# XC7A35TFTG256_power.net
KiCad netlist of a schematic drawn in Altium Designer
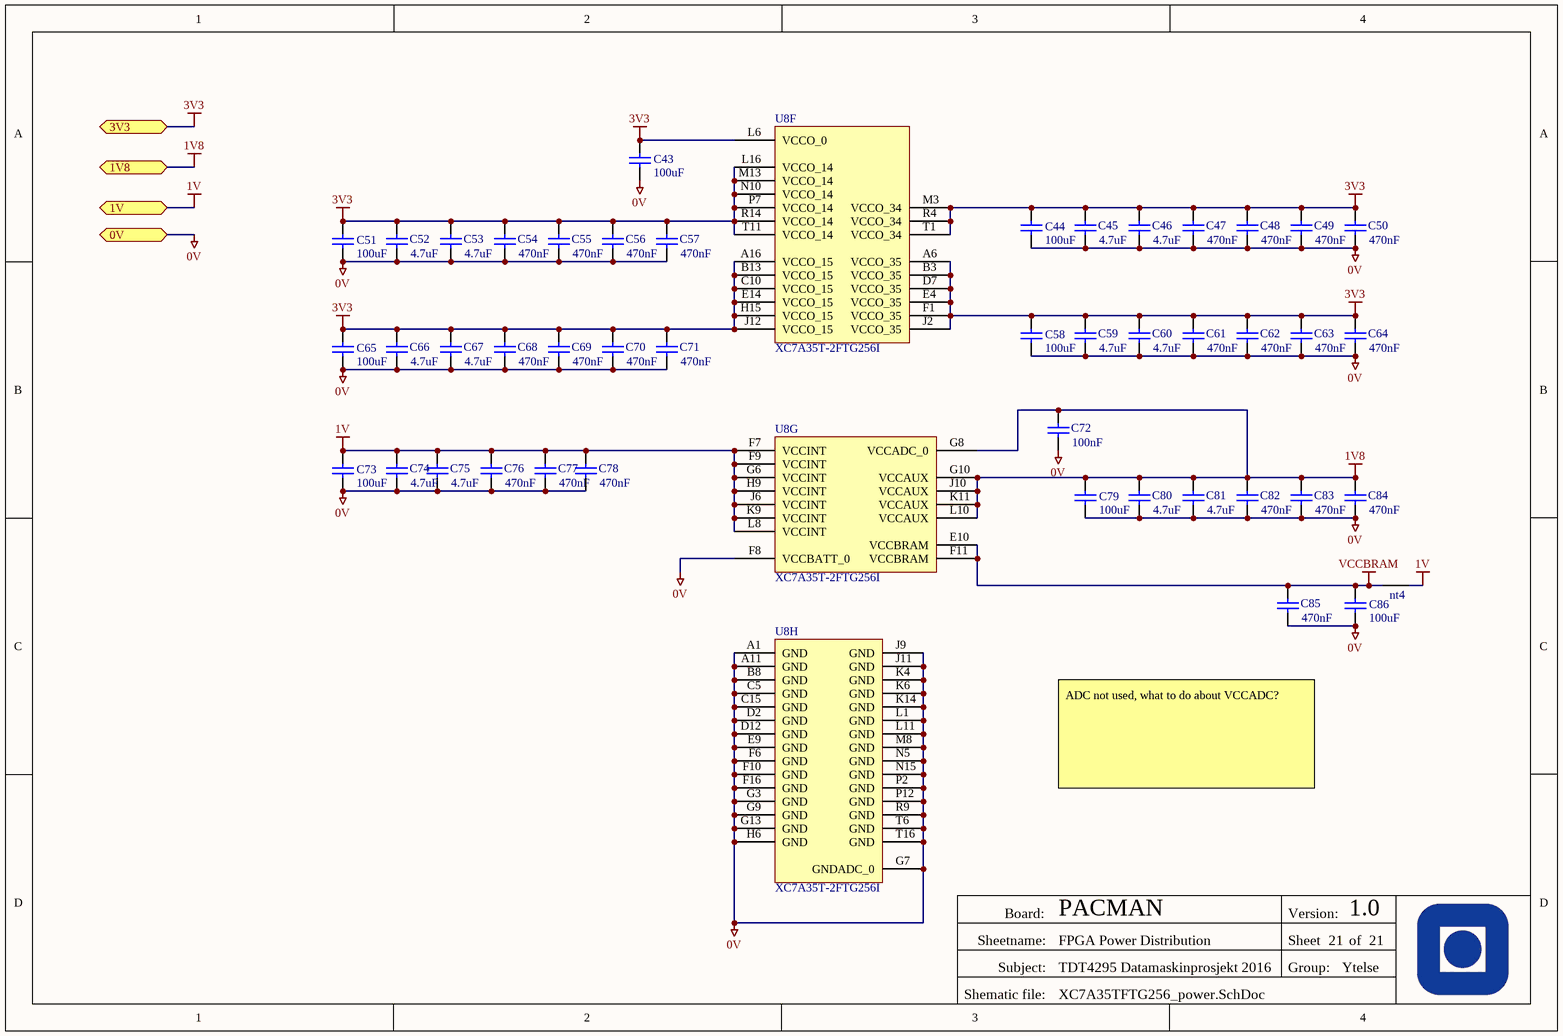
[diagram p0: XC7A35TFTG256_power.SchDoc]

(export (version "E")
  (design (tool "Eeschema 10.0.6"))
  (components
    (comp (ref "C43")
      (value "100uF")
      (footprint "CAPC1210(3225)250_N")
      (description "1210 100uF capacitor for artix-7 power decoupling")
      (fields (field (name "Comment") "GRM32ER60J107ME20L"))
      (libsource (lib "dmpro16lib") (part "GRM32ER60J107ME20L"))
    )
    (comp (ref "C44")
      (value "100uF")
      (footprint "CAPC1210(3225)250_N")
      (description "1210 100uF capacitor for artix-7 power decoupling")
      (fields (field (name "Comment") "GRM32ER60J107ME20L"))
      (libsource (lib "dmpro16lib") (part "GRM32ER60J107ME20L"))
    )
    (comp (ref "C45")
      (value "4.7uF")
      (footprint "CAPC0603(1608)100_M")
      (description "CAP 4.7uF 10V ±10% 0603 (1608 Metric) Thickness 1mm SMD")
      (fields (field (name "TOLERANCE") "Â±10%") (field (name "Comment") "CAP 4.7uF 10V 0603(1608)"))
      (libsource (lib "Altium Content Vault") (part "CMP-1035-02785-1"))
    )
    (comp (ref "C46")
      (value "4.7uF")
      (footprint "CAPC0603(1608)100_M")
      (description "CAP 4.7uF 10V ±10% 0603 (1608 Metric) Thickness 1mm SMD")
      (fields (field (name "TOLERANCE") "Â±10%") (field (name "Comment") "CAP 4.7uF 10V 0603(1608)"))
      (libsource (lib "Altium Content Vault") (part "CMP-1035-02785-1"))
    )
    (comp (ref "C47")
      (value "470nF")
      (footprint "CAPC0603(1608)100_L")
      (description "CAP 470nF 10V ±5% 0603 (1608 Metric) Thickness 1mm SMD")
      (fields (field (name "TOLERANCE") "Â±5%") (field (name "Comment") "CAP 470nF 10V 0603(1608)"))
      (libsource (lib "Altium Content Vault") (part "CMP-1035-02695-1"))
    )
    (comp (ref "C48")
      (value "470nF")
      (footprint "CAPC0603(1608)100_L")
      (description "CAP 470nF 10V ±5% 0603 (1608 Metric) Thickness 1mm SMD")
      (fields (field (name "TOLERANCE") "Â±5%") (field (name "Comment") "CAP 470nF 10V 0603(1608)"))
      (libsource (lib "Altium Content Vault") (part "CMP-1035-02695-1"))
    )
    (comp (ref "C49")
      (value "470nF")
      (footprint "CAPC0603(1608)100_L")
      (description "CAP 470nF 10V ±5% 0603 (1608 Metric) Thickness 1mm SMD")
      (fields (field (name "TOLERANCE") "Â±5%") (field (name "Comment") "CAP 470nF 10V 0603(1608)"))
      (libsource (lib "Altium Content Vault") (part "CMP-1035-02695-1"))
    )
    (comp (ref "C50")
      (value "470nF")
      (footprint "CAPC0603(1608)100_L")
      (description "CAP 470nF 10V ±5% 0603 (1608 Metric) Thickness 1mm SMD")
      (fields (field (name "TOLERANCE") "Â±5%") (field (name "Comment") "CAP 470nF 10V 0603(1608)"))
      (libsource (lib "Altium Content Vault") (part "CMP-1035-02695-1"))
    )
    (comp (ref "C51")
      (value "100uF")
      (footprint "CAPC1210(3225)250_N")
      (description "1210 100uF capacitor for artix-7 power decoupling")
      (fields (field (name "Comment") "GRM32ER60J107ME20L"))
      (libsource (lib "dmpro16lib") (part "GRM32ER60J107ME20L"))
    )
    (comp (ref "C52")
      (value "4.7uF")
      (footprint "CAPC0603(1608)100_M")
      (description "CAP 4.7uF 10V ±10% 0603 (1608 Metric) Thickness 1mm SMD")
      (fields (field (name "TOLERANCE") "Â±10%") (field (name "Comment") "CAP 4.7uF 10V 0603(1608)"))
      (libsource (lib "Altium Content Vault") (part "CMP-1035-02785-1"))
    )
    (comp (ref "C53")
      (value "4.7uF")
      (footprint "CAPC0603(1608)100_M")
      (description "CAP 4.7uF 10V ±10% 0603 (1608 Metric) Thickness 1mm SMD")
      (fields (field (name "TOLERANCE") "Â±10%") (field (name "Comment") "CAP 4.7uF 10V 0603(1608)"))
      (libsource (lib "Altium Content Vault") (part "CMP-1035-02785-1"))
    )
    (comp (ref "C54")
      (value "470nF")
      (footprint "CAPC0603(1608)100_L")
      (description "CAP 470nF 10V ±5% 0603 (1608 Metric) Thickness 1mm SMD")
      (fields (field (name "TOLERANCE") "Â±5%") (field (name "Comment") "CAP 470nF 10V 0603(1608)"))
      (libsource (lib "Altium Content Vault") (part "CMP-1035-02695-1"))
    )
    (comp (ref "C55")
      (value "470nF")
      (footprint "CAPC0603(1608)100_L")
      (description "CAP 470nF 10V ±5% 0603 (1608 Metric) Thickness 1mm SMD")
      (fields (field (name "TOLERANCE") "Â±5%") (field (name "Comment") "CAP 470nF 10V 0603(1608)"))
      (libsource (lib "Altium Content Vault") (part "CMP-1035-02695-1"))
    )
    (comp (ref "C56")
      (value "470nF")
      (footprint "CAPC0603(1608)100_L")
      (description "CAP 470nF 10V ±5% 0603 (1608 Metric) Thickness 1mm SMD")
      (fields (field (name "TOLERANCE") "Â±5%") (field (name "Comment") "CAP 470nF 10V 0603(1608)"))
      (libsource (lib "Altium Content Vault") (part "CMP-1035-02695-1"))
    )
    (comp (ref "C57")
      (value "470nF")
      (footprint "CAPC0603(1608)100_L")
      (description "CAP 470nF 10V ±5% 0603 (1608 Metric) Thickness 1mm SMD")
      (fields (field (name "TOLERANCE") "Â±5%") (field (name "Comment") "CAP 470nF 10V 0603(1608)"))
      (libsource (lib "Altium Content Vault") (part "CMP-1035-02695-1"))
    )
    (comp (ref "C58")
      (value "100uF")
      (footprint "CAPC1210(3225)250_N")
      (description "1210 100uF capacitor for artix-7 power decoupling")
      (fields (field (name "Comment") "GRM32ER60J107ME20L"))
      (libsource (lib "dmpro16lib") (part "GRM32ER60J107ME20L"))
    )
    (comp (ref "C59")
      (value "4.7uF")
      (footprint "CAPC0603(1608)100_M")
      (description "CAP 4.7uF 10V ±10% 0603 (1608 Metric) Thickness 1mm SMD")
      (fields (field (name "TOLERANCE") "Â±10%") (field (name "Comment") "CAP 4.7uF 10V 0603(1608)"))
      (libsource (lib "Altium Content Vault") (part "CMP-1035-02785-1"))
    )
    (comp (ref "C60")
      (value "4.7uF")
      (footprint "CAPC0603(1608)100_M")
      (description "CAP 4.7uF 10V ±10% 0603 (1608 Metric) Thickness 1mm SMD")
      (fields (field (name "TOLERANCE") "Â±10%") (field (name "Comment") "CAP 4.7uF 10V 0603(1608)"))
      (libsource (lib "Altium Content Vault") (part "CMP-1035-02785-1"))
    )
    (comp (ref "C61")
      (value "470nF")
      (footprint "CAPC0603(1608)100_L")
      (description "CAP 470nF 10V ±5% 0603 (1608 Metric) Thickness 1mm SMD")
      (fields (field (name "TOLERANCE") "Â±5%") (field (name "Comment") "CAP 470nF 10V 0603(1608)"))
      (libsource (lib "Altium Content Vault") (part "CMP-1035-02695-1"))
    )
    (comp (ref "C62")
      (value "470nF")
      (footprint "CAPC0603(1608)100_L")
      (description "CAP 470nF 10V ±5% 0603 (1608 Metric) Thickness 1mm SMD")
      (fields (field (name "TOLERANCE") "Â±5%") (field (name "Comment") "CAP 470nF 10V 0603(1608)"))
      (libsource (lib "Altium Content Vault") (part "CMP-1035-02695-1"))
    )
    (comp (ref "C63")
      (value "470nF")
      (footprint "CAPC0603(1608)100_L")
      (description "CAP 470nF 10V ±5% 0603 (1608 Metric) Thickness 1mm SMD")
      (fields (field (name "TOLERANCE") "Â±5%") (field (name "Comment") "CAP 470nF 10V 0603(1608)"))
      (libsource (lib "Altium Content Vault") (part "CMP-1035-02695-1"))
    )
    (comp (ref "C64")
      (value "470nF")
      (footprint "CAPC0603(1608)100_L")
      (description "CAP 470nF 10V ±5% 0603 (1608 Metric) Thickness 1mm SMD")
      (fields (field (name "TOLERANCE") "Â±5%") (field (name "Comment") "CAP 470nF 10V 0603(1608)"))
      (libsource (lib "Altium Content Vault") (part "CMP-1035-02695-1"))
    )
    (comp (ref "C65")
      (value "100uF")
      (footprint "CAPC1210(3225)250_N")
      (description "1210 100uF capacitor for artix-7 power decoupling")
      (fields (field (name "Comment") "GRM32ER60J107ME20L"))
      (libsource (lib "dmpro16lib") (part "GRM32ER60J107ME20L"))
    )
    (comp (ref "C66")
      (value "4.7uF")
      (footprint "CAPC0603(1608)100_M")
      (description "CAP 4.7uF 10V ±10% 0603 (1608 Metric) Thickness 1mm SMD")
      (fields (field (name "TOLERANCE") "Â±10%") (field (name "Comment") "CAP 4.7uF 10V 0603(1608)"))
      (libsource (lib "Altium Content Vault") (part "CMP-1035-02785-1"))
    )
    (comp (ref "C67")
      (value "4.7uF")
      (footprint "CAPC0603(1608)100_M")
      (description "CAP 4.7uF 10V ±10% 0603 (1608 Metric) Thickness 1mm SMD")
      (fields (field (name "TOLERANCE") "Â±10%") (field (name "Comment") "CAP 4.7uF 10V 0603(1608)"))
      (libsource (lib "Altium Content Vault") (part "CMP-1035-02785-1"))
    )
    (comp (ref "C68")
      (value "470nF")
      (footprint "CAPC0603(1608)100_L")
      (description "CAP 470nF 10V ±5% 0603 (1608 Metric) Thickness 1mm SMD")
      (fields (field (name "TOLERANCE") "Â±5%") (field (name "Comment") "CAP 470nF 10V 0603(1608)"))
      (libsource (lib "Altium Content Vault") (part "CMP-1035-02695-1"))
    )
    (comp (ref "C69")
      (value "470nF")
      (footprint "CAPC0603(1608)100_L")
      (description "CAP 470nF 10V ±5% 0603 (1608 Metric) Thickness 1mm SMD")
      (fields (field (name "TOLERANCE") "Â±5%") (field (name "Comment") "CAP 470nF 10V 0603(1608)"))
      (libsource (lib "Altium Content Vault") (part "CMP-1035-02695-1"))
    )
    (comp (ref "C70")
      (value "470nF")
      (footprint "CAPC0603(1608)100_L")
      (description "CAP 470nF 10V ±5% 0603 (1608 Metric) Thickness 1mm SMD")
      (fields (field (name "TOLERANCE") "Â±5%") (field (name "Comment") "CAP 470nF 10V 0603(1608)"))
      (libsource (lib "Altium Content Vault") (part "CMP-1035-02695-1"))
    )
    (comp (ref "C71")
      (value "470nF")
      (footprint "CAPC0603(1608)100_L")
      (description "CAP 470nF 10V ±5% 0603 (1608 Metric) Thickness 1mm SMD")
      (fields (field (name "TOLERANCE") "Â±5%") (field (name "Comment") "CAP 470nF 10V 0603(1608)"))
      (libsource (lib "Altium Content Vault") (part "CMP-1035-02695-1"))
    )
    (comp (ref "C72")
      (value "100nF")
      (footprint "CAPC0603(1608)100_M")
      (description "CAP 100nF 16V ±5% 0603 (1608 Metric) Thickness 1mm SMD")
      (fields (field (name "TOLERANCE") "Â±5%") (field (name "Comment") "CAP 100nF 16V 0603(1608)"))
      (libsource (lib "Altium Content Vault") (part "CMP-1035-02583-1"))
    )
    (comp (ref "C73")
      (value "100uF")
      (footprint "CAPC1210(3225)250_N")
      (description "1210 100uF capacitor for artix-7 power decoupling")
      (fields (field (name "Comment") "GRM32ER60J107ME20L"))
      (libsource (lib "dmpro16lib") (part "GRM32ER60J107ME20L"))
    )
    (comp (ref "C74")
      (value "4.7uF")
      (footprint "CAPC0603(1608)100_M")
      (description "CAP 4.7uF 10V ±10% 0603 (1608 Metric) Thickness 1mm SMD")
      (fields (field (name "TOLERANCE") "Â±10%") (field (name "Comment") "CAP 4.7uF 10V 0603(1608)"))
      (libsource (lib "Altium Content Vault") (part "CMP-1035-02785-1"))
    )
    (comp (ref "C75")
      (value "4.7uF")
      (footprint "CAPC0603(1608)100_M")
      (description "CAP 4.7uF 10V ±10% 0603 (1608 Metric) Thickness 1mm SMD")
      (fields (field (name "TOLERANCE") "Â±10%") (field (name "Comment") "CAP 4.7uF 10V 0603(1608)"))
      (libsource (lib "Altium Content Vault") (part "CMP-1035-02785-1"))
    )
    (comp (ref "C76")
      (value "470nF")
      (footprint "CAPC0603(1608)100_L")
      (description "CAP 470nF 10V ±5% 0603 (1608 Metric) Thickness 1mm SMD")
      (fields (field (name "TOLERANCE") "Â±5%") (field (name "Comment") "CAP 470nF 10V 0603(1608)"))
      (libsource (lib "Altium Content Vault") (part "CMP-1035-02695-1"))
    )
    (comp (ref "C77")
      (value "470nF")
      (footprint "CAPC0603(1608)100_L")
      (description "CAP 470nF 10V ±5% 0603 (1608 Metric) Thickness 1mm SMD")
      (fields (field (name "TOLERANCE") "Â±5%") (field (name "Comment") "CAP 470nF 10V 0603(1608)"))
      (libsource (lib "Altium Content Vault") (part "CMP-1035-02695-1"))
    )
    (comp (ref "C78")
      (value "470nF")
      (footprint "CAPC0603(1608)100_L")
      (description "CAP 470nF 10V ±5% 0603 (1608 Metric) Thickness 1mm SMD")
      (fields (field (name "TOLERANCE") "Â±5%") (field (name "Comment") "CAP 470nF 10V 0603(1608)"))
      (libsource (lib "Altium Content Vault") (part "CMP-1035-02695-1"))
    )
    (comp (ref "C79")
      (value "100uF")
      (footprint "CAPC1210(3225)250_N")
      (description "1210 100uF capacitor for artix-7 power decoupling")
      (fields (field (name "Comment") "GRM32ER60J107ME20L"))
      (libsource (lib "dmpro16lib") (part "GRM32ER60J107ME20L"))
    )
    (comp (ref "C80")
      (value "4.7uF")
      (footprint "CAPC0603(1608)100_M")
      (description "CAP 4.7uF 10V ±10% 0603 (1608 Metric) Thickness 1mm SMD")
      (fields (field (name "TOLERANCE") "Â±10%") (field (name "Comment") "CAP 4.7uF 10V 0603(1608)"))
      (libsource (lib "Altium Content Vault") (part "CMP-1035-02785-1"))
    )
    (comp (ref "C81")
      (value "4.7uF")
      (footprint "CAPC0603(1608)100_M")
      (description "CAP 4.7uF 10V ±10% 0603 (1608 Metric) Thickness 1mm SMD")
      (fields (field (name "TOLERANCE") "Â±10%") (field (name "Comment") "CAP 4.7uF 10V 0603(1608)"))
      (libsource (lib "Altium Content Vault") (part "CMP-1035-02785-1"))
    )
    (comp (ref "C82")
      (value "470nF")
      (footprint "CAPC0603(1608)100_L")
      (description "CAP 470nF 10V ±5% 0603 (1608 Metric) Thickness 1mm SMD")
      (fields (field (name "TOLERANCE") "Â±5%") (field (name "Comment") "CAP 470nF 10V 0603(1608)"))
      (libsource (lib "Altium Content Vault") (part "CMP-1035-02695-1"))
    )
    (comp (ref "C83")
      (value "470nF")
      (footprint "CAPC0603(1608)100_L")
      (description "CAP 470nF 10V ±5% 0603 (1608 Metric) Thickness 1mm SMD")
      (fields (field (name "TOLERANCE") "Â±5%") (field (name "Comment") "CAP 470nF 10V 0603(1608)"))
      (libsource (lib "Altium Content Vault") (part "CMP-1035-02695-1"))
    )
    (comp (ref "C84")
      (value "470nF")
      (footprint "CAPC0603(1608)100_L")
      (description "CAP 470nF 10V ±5% 0603 (1608 Metric) Thickness 1mm SMD")
      (fields (field (name "TOLERANCE") "Â±5%") (field (name "Comment") "CAP 470nF 10V 0603(1608)"))
      (libsource (lib "Altium Content Vault") (part "CMP-1035-02695-1"))
    )
    (comp (ref "C85")
      (value "470nF")
      (footprint "CAPC0603(1608)100_L")
      (description "CAP 470nF 10V ±5% 0603 (1608 Metric) Thickness 1mm SMD")
      (fields (field (name "TOLERANCE") "Â±5%") (field (name "Comment") "CAP 470nF 10V 0603(1608)"))
      (libsource (lib "Altium Content Vault") (part "CMP-1035-02695-1"))
    )
    (comp (ref "C86")
      (value "100uF")
      (footprint "CAPC1210(3225)250_N")
      (description "1210 100uF capacitor for artix-7 power decoupling")
      (fields (field (name "Comment") "GRM32ER60J107ME20L"))
      (libsource (lib "dmpro16lib") (part "GRM32ER60J107ME20L"))
    )
    (comp (ref "nt4")
      (value "net tie")
      (footprint "net tie")
      (description "used to connect nets without transferring net name")
      (libsource (lib "dmpro16lib") (part "net tie"))
    )
    (comp (ref "U8")
      (value "XC7A35T-2FTG256I")
      (footprint "FTG256")
      (description "Artix-7 FPGA, 170 User I/Os, 0 GTP, 256-Ball BGA, Speed Grade 2, Industrial Grade, Pb-Free")
      (fields (field (name "MANUFACTURER") "Xilinx"))
      (libsource (lib "Altium Content Vault") (part "XLNX-XC7A35T-FTG256"))
    )
  )
  (nets
    (net (code "1") (name "0V") (class "Default")
      (node (ref "C43") (pin "1") (pinfunction "1_1") (pintype "passive"))
      (node (ref "C44") (pin "1") (pinfunction "1_1") (pintype "passive"))
      (node (ref "C45") (pin "1") (pinfunction "1_1") (pintype "passive"))
      (node (ref "C46") (pin "1") (pinfunction "1_1") (pintype "passive"))
      (node (ref "C47") (pin "1") (pinfunction "1_1") (pintype "passive"))
      (node (ref "C48") (pin "1") (pinfunction "1_1") (pintype "passive"))
      (node (ref "C49") (pin "1") (pinfunction "1_1") (pintype "passive"))
      (node (ref "C50") (pin "1") (pinfunction "1_1") (pintype "passive"))
      (node (ref "C51") (pin "1") (pinfunction "1_1") (pintype "passive"))
      (node (ref "C52") (pin "1") (pinfunction "1_1") (pintype "passive"))
      (node (ref "C53") (pin "1") (pinfunction "1_1") (pintype "passive"))
      (node (ref "C54") (pin "1") (pinfunction "1_1") (pintype "passive"))
      (node (ref "C55") (pin "1") (pinfunction "1_1") (pintype "passive"))
      (node (ref "C56") (pin "1") (pinfunction "1_1") (pintype "passive"))
      (node (ref "C57") (pin "1") (pinfunction "1_1") (pintype "passive"))
      (node (ref "C58") (pin "1") (pinfunction "1_1") (pintype "passive"))
      (node (ref "C59") (pin "1") (pinfunction "1_1") (pintype "passive"))
      (node (ref "C60") (pin "1") (pinfunction "1_1") (pintype "passive"))
      (node (ref "C61") (pin "1") (pinfunction "1_1") (pintype "passive"))
      (node (ref "C62") (pin "1") (pinfunction "1_1") (pintype "passive"))
      (node (ref "C63") (pin "1") (pinfunction "1_1") (pintype "passive"))
      (node (ref "C64") (pin "1") (pinfunction "1_1") (pintype "passive"))
      (node (ref "C65") (pin "1") (pinfunction "1_1") (pintype "passive"))
      (node (ref "C66") (pin "1") (pinfunction "1_1") (pintype "passive"))
      (node (ref "C67") (pin "1") (pinfunction "1_1") (pintype "passive"))
      (node (ref "C68") (pin "1") (pinfunction "1_1") (pintype "passive"))
      (node (ref "C69") (pin "1") (pinfunction "1_1") (pintype "passive"))
      (node (ref "C70") (pin "1") (pinfunction "1_1") (pintype "passive"))
      (node (ref "C71") (pin "1") (pinfunction "1_1") (pintype "passive"))
      (node (ref "C72") (pin "1") (pinfunction "1_1") (pintype "passive"))
      (node (ref "C73") (pin "1") (pinfunction "1_1") (pintype "passive"))
      (node (ref "C74") (pin "1") (pinfunction "1_1") (pintype "passive"))
      (node (ref "C75") (pin "1") (pinfunction "1_1") (pintype "passive"))
      (node (ref "C76") (pin "1") (pinfunction "1_1") (pintype "passive"))
      (node (ref "C77") (pin "1") (pinfunction "1_1") (pintype "passive"))
      (node (ref "C78") (pin "1") (pinfunction "1_1") (pintype "passive"))
      (node (ref "C79") (pin "1") (pinfunction "1_1") (pintype "passive"))
      (node (ref "C80") (pin "1") (pinfunction "1_1") (pintype "passive"))
      (node (ref "C81") (pin "1") (pinfunction "1_1") (pintype "passive"))
      (node (ref "C82") (pin "1") (pinfunction "1_1") (pintype "passive"))
      (node (ref "C83") (pin "1") (pinfunction "1_1") (pintype "passive"))
      (node (ref "C84") (pin "1") (pinfunction "1_1") (pintype "passive"))
      (node (ref "C85") (pin "1") (pinfunction "1_1") (pintype "passive"))
      (node (ref "C86") (pin "1") (pinfunction "1_1") (pintype "passive"))
      (node (ref "U8") (pin "A1") (pinfunction "GND_A1") (pintype "power_in"))
      (node (ref "U8") (pin "A11") (pinfunction "GND_A11") (pintype "power_in"))
      (node (ref "U8") (pin "B8") (pinfunction "GND_B8") (pintype "power_in"))
      (node (ref "U8") (pin "C15") (pinfunction "GND_C15") (pintype "power_in"))
      (node (ref "U8") (pin "C5") (pinfunction "GND_C5") (pintype "power_in"))
      (node (ref "U8") (pin "D12") (pinfunction "GND_D12") (pintype "power_in"))
      (node (ref "U8") (pin "D2") (pinfunction "GND_D2") (pintype "power_in"))
      (node (ref "U8") (pin "E9") (pinfunction "GND_E9") (pintype "power_in"))
      (node (ref "U8") (pin "F10") (pinfunction "GND_F10") (pintype "power_in"))
      (node (ref "U8") (pin "F16") (pinfunction "GND_F16") (pintype "power_in"))
      (node (ref "U8") (pin "F6") (pinfunction "GND_F6") (pintype "power_in"))
      (node (ref "U8") (pin "F8") (pinfunction "VCCBATT_0_F8") (pintype "power_in"))
      (node (ref "U8") (pin "G13") (pinfunction "GND_G13") (pintype "power_in"))
      (node (ref "U8") (pin "G3") (pinfunction "GND_G3") (pintype "power_in"))
      (node (ref "U8") (pin "G7") (pinfunction "GNDADC_0_G7") (pintype "power_in"))
      (node (ref "U8") (pin "G9") (pinfunction "GND_G9") (pintype "power_in"))
      (node (ref "U8") (pin "H6") (pinfunction "GND_H6") (pintype "power_in"))
      (node (ref "U8") (pin "J11") (pinfunction "GND_J11") (pintype "power_in"))
      (node (ref "U8") (pin "J9") (pinfunction "GND_J9") (pintype "power_in"))
      (node (ref "U8") (pin "K14") (pinfunction "GND_K14") (pintype "power_in"))
      (node (ref "U8") (pin "K4") (pinfunction "GND_K4") (pintype "power_in"))
      (node (ref "U8") (pin "K6") (pinfunction "GND_K6") (pintype "power_in"))
      (node (ref "U8") (pin "L1") (pinfunction "GND_L1") (pintype "power_in"))
      (node (ref "U8") (pin "L11") (pinfunction "GND_L11") (pintype "power_in"))
      (node (ref "U8") (pin "M8") (pinfunction "GND_M8") (pintype "power_in"))
      (node (ref "U8") (pin "N15") (pinfunction "GND_N15") (pintype "power_in"))
      (node (ref "U8") (pin "N5") (pinfunction "GND_N5") (pintype "power_in"))
      (node (ref "U8") (pin "P12") (pinfunction "GND_P12") (pintype "power_in"))
      (node (ref "U8") (pin "P2") (pinfunction "GND_P2") (pintype "power_in"))
      (node (ref "U8") (pin "R9") (pinfunction "GND_R9") (pintype "power_in"))
      (node (ref "U8") (pin "T16") (pinfunction "GND_T16") (pintype "power_in"))
      (node (ref "U8") (pin "T6") (pinfunction "GND_T6") (pintype "power_in"))
    )
    (net (code "2") (name "1V") (class "Default")
      (node (ref "C73") (pin "2") (pinfunction "2_2") (pintype "passive"))
      (node (ref "C74") (pin "2") (pinfunction "2_2") (pintype "passive"))
      (node (ref "C75") (pin "2") (pinfunction "2_2") (pintype "passive"))
      (node (ref "C76") (pin "2") (pinfunction "2_2") (pintype "passive"))
      (node (ref "C77") (pin "2") (pinfunction "2_2") (pintype "passive"))
      (node (ref "C78") (pin "2") (pinfunction "2_2") (pintype "passive"))
      (node (ref "U8") (pin "F7") (pinfunction "VCCINT_F7") (pintype "power_in"))
      (node (ref "U8") (pin "F9") (pinfunction "VCCINT_F9") (pintype "power_in"))
      (node (ref "U8") (pin "G6") (pinfunction "VCCINT_G6") (pintype "power_in"))
      (node (ref "U8") (pin "H9") (pinfunction "VCCINT_H9") (pintype "power_in"))
      (node (ref "U8") (pin "J6") (pinfunction "VCCINT_J6") (pintype "power_in"))
      (node (ref "U8") (pin "K9") (pinfunction "VCCINT_K9") (pintype "power_in"))
      (node (ref "U8") (pin "L8") (pinfunction "VCCINT_L8") (pintype "power_in"))
      (node (ref "nt4") (pin "1") (pinfunction "1_1") (pintype "passive"))
    )
    (net (code "3") (name "1V8") (class "Default")
      (node (ref "C72") (pin "2") (pinfunction "2_2") (pintype "passive"))
      (node (ref "C79") (pin "2") (pinfunction "2_2") (pintype "passive"))
      (node (ref "C80") (pin "2") (pinfunction "2_2") (pintype "passive"))
      (node (ref "C81") (pin "2") (pinfunction "2_2") (pintype "passive"))
      (node (ref "C82") (pin "2") (pinfunction "2_2") (pintype "passive"))
      (node (ref "C83") (pin "2") (pinfunction "2_2") (pintype "passive"))
      (node (ref "C84") (pin "2") (pinfunction "2_2") (pintype "passive"))
      (node (ref "U8") (pin "G10") (pinfunction "VCCAUX_G10") (pintype "power_in"))
      (node (ref "U8") (pin "G8") (pinfunction "VCCADC_0_G8") (pintype "power_in"))
      (node (ref "U8") (pin "J10") (pinfunction "VCCAUX_J10") (pintype "power_in"))
      (node (ref "U8") (pin "K11") (pinfunction "VCCAUX_K11") (pintype "power_in"))
      (node (ref "U8") (pin "L10") (pinfunction "VCCAUX_L10") (pintype "power_in"))
    )
    (net (code "4") (name "3V3") (class "Default")
      (node (ref "C43") (pin "2") (pinfunction "2_2") (pintype "passive"))
      (node (ref "C44") (pin "2") (pinfunction "2_2") (pintype "passive"))
      (node (ref "C45") (pin "2") (pinfunction "2_2") (pintype "passive"))
      (node (ref "C46") (pin "2") (pinfunction "2_2") (pintype "passive"))
      (node (ref "C47") (pin "2") (pinfunction "2_2") (pintype "passive"))
      (node (ref "C48") (pin "2") (pinfunction "2_2") (pintype "passive"))
      (node (ref "C49") (pin "2") (pinfunction "2_2") (pintype "passive"))
      (node (ref "C50") (pin "2") (pinfunction "2_2") (pintype "passive"))
      (node (ref "C51") (pin "2") (pinfunction "2_2") (pintype "passive"))
      (node (ref "C52") (pin "2") (pinfunction "2_2") (pintype "passive"))
      (node (ref "C53") (pin "2") (pinfunction "2_2") (pintype "passive"))
      (node (ref "C54") (pin "2") (pinfunction "2_2") (pintype "passive"))
      (node (ref "C55") (pin "2") (pinfunction "2_2") (pintype "passive"))
      (node (ref "C56") (pin "2") (pinfunction "2_2") (pintype "passive"))
      (node (ref "C57") (pin "2") (pinfunction "2_2") (pintype "passive"))
      (node (ref "C58") (pin "2") (pinfunction "2_2") (pintype "passive"))
      (node (ref "C59") (pin "2") (pinfunction "2_2") (pintype "passive"))
      (node (ref "C60") (pin "2") (pinfunction "2_2") (pintype "passive"))
      (node (ref "C61") (pin "2") (pinfunction "2_2") (pintype "passive"))
      (node (ref "C62") (pin "2") (pinfunction "2_2") (pintype "passive"))
      (node (ref "C63") (pin "2") (pinfunction "2_2") (pintype "passive"))
      (node (ref "C64") (pin "2") (pinfunction "2_2") (pintype "passive"))
      (node (ref "C65") (pin "2") (pinfunction "2_2") (pintype "passive"))
      (node (ref "C66") (pin "2") (pinfunction "2_2") (pintype "passive"))
      (node (ref "C67") (pin "2") (pinfunction "2_2") (pintype "passive"))
      (node (ref "C68") (pin "2") (pinfunction "2_2") (pintype "passive"))
      (node (ref "C69") (pin "2") (pinfunction "2_2") (pintype "passive"))
      (node (ref "C70") (pin "2") (pinfunction "2_2") (pintype "passive"))
      (node (ref "C71") (pin "2") (pinfunction "2_2") (pintype "passive"))
      (node (ref "U8") (pin "A16") (pinfunction "VCCO_15_A16") (pintype "power_in"))
      (node (ref "U8") (pin "A6") (pinfunction "VCCO_35_A6") (pintype "power_in"))
      (node (ref "U8") (pin "B13") (pinfunction "VCCO_15_B13") (pintype "power_in"))
      (node (ref "U8") (pin "B3") (pinfunction "VCCO_35_B3") (pintype "power_in"))
      (node (ref "U8") (pin "C10") (pinfunction "VCCO_15_C10") (pintype "power_in"))
      (node (ref "U8") (pin "D7") (pinfunction "VCCO_35_D7") (pintype "power_in"))
      (node (ref "U8") (pin "E14") (pinfunction "VCCO_15_E14") (pintype "power_in"))
      (node (ref "U8") (pin "E4") (pinfunction "VCCO_35_E4") (pintype "power_in"))
      (node (ref "U8") (pin "F1") (pinfunction "VCCO_35_F1") (pintype "power_in"))
      (node (ref "U8") (pin "H15") (pinfunction "VCCO_15_H15") (pintype "power_in"))
      (node (ref "U8") (pin "J12") (pinfunction "VCCO_15_J12") (pintype "power_in"))
      (node (ref "U8") (pin "J2") (pinfunction "VCCO_35_J2") (pintype "power_in"))
      (node (ref "U8") (pin "L16") (pinfunction "VCCO_14_L16") (pintype "power_in"))
      (node (ref "U8") (pin "L6") (pinfunction "VCCO_0_L6") (pintype "power_in"))
      (node (ref "U8") (pin "M13") (pinfunction "VCCO_14_M13") (pintype "power_in"))
      (node (ref "U8") (pin "M3") (pinfunction "VCCO_34_M3") (pintype "power_in"))
      (node (ref "U8") (pin "N10") (pinfunction "VCCO_14_N10") (pintype "power_in"))
      (node (ref "U8") (pin "P7") (pinfunction "VCCO_14_P7") (pintype "power_in"))
      (node (ref "U8") (pin "R14") (pinfunction "VCCO_14_R14") (pintype "power_in"))
      (node (ref "U8") (pin "R4") (pinfunction "VCCO_34_R4") (pintype "power_in"))
      (node (ref "U8") (pin "T1") (pinfunction "VCCO_34_T1") (pintype "power_in"))
      (node (ref "U8") (pin "T11") (pinfunction "VCCO_14_T11") (pintype "power_in"))
    )
    (net (code "5") (name "VCCBRAM") (class "Default")
      (node (ref "C85") (pin "2") (pinfunction "2_2") (pintype "passive"))
      (node (ref "C86") (pin "2") (pinfunction "2_2") (pintype "passive"))
      (node (ref "U8") (pin "E10") (pinfunction "VCCBRAM_E10") (pintype "power_in"))
      (node (ref "U8") (pin "F11") (pinfunction "VCCBRAM_F11") (pintype "power_in"))
      (node (ref "nt4") (pin "0") (pinfunction "0_0") (pintype "passive"))
    )
  )
)
